# Connections.net
KiCad netlist of a schematic drawn in Altium Designer
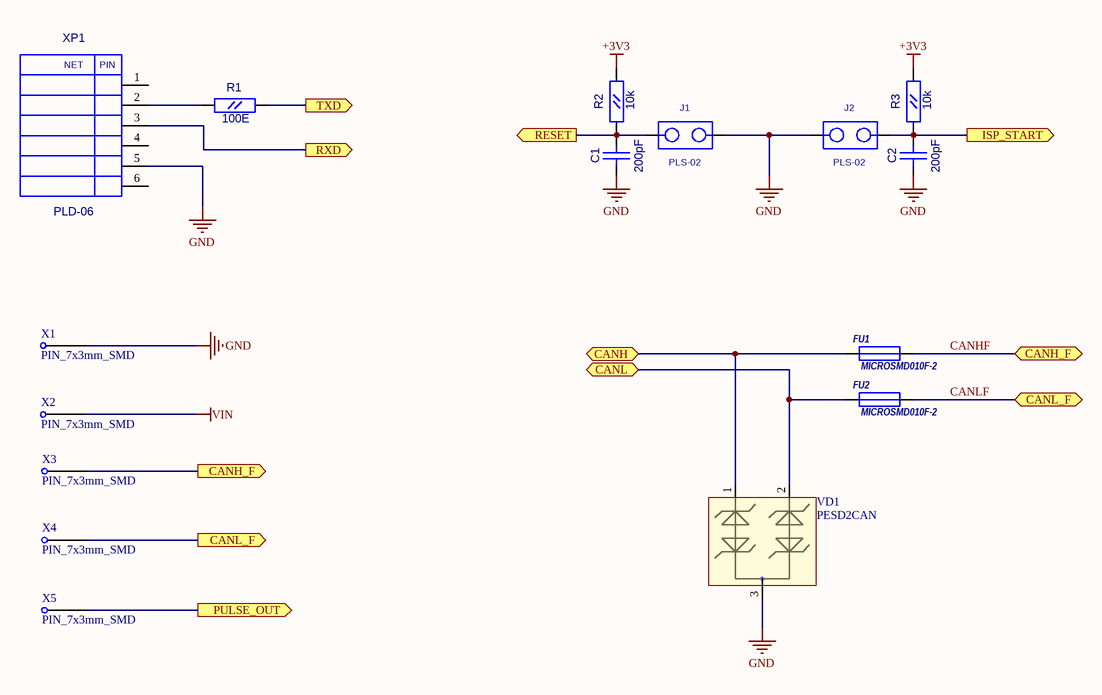
[diagram p0: Connections.SchDoc]

(export (version "E")
  (design (tool "Eeschema 10.0.6"))
  (components
    (comp (ref "C1")
      (value "200pF")
      (footprint "CC0603")
      (description "CC0603")
      (libsource (lib "gprs_modem_2") (part "CC0603"))
    )
    (comp (ref "C2")
      (value "200pF")
      (footprint "CC0603")
      (description "CC0603")
      (libsource (lib "gprs_modem_2") (part "CC0603"))
    )
    (comp (ref "FU1")
      (value "MICROSMD010F-2")
      (footprint "RC1210")
      (description "MICROSMD")
      (libsource (lib "gprs_modem_2") (part "MICROSMD"))
    )
    (comp (ref "FU2")
      (value "MICROSMD010F-2")
      (footprint "RC1210")
      (description "MICROSMD")
      (libsource (lib "gprs_modem_2") (part "MICROSMD"))
    )
    (comp (ref "J1") (value "PLS-02") (footprint "PLS-02") (libsource (lib "gprs_modem_2") (part "PLS-02")))
    (comp (ref "J2") (value "PLS-02") (footprint "PLS-02") (libsource (lib "gprs_modem_2") (part "PLS-02")))
    (comp (ref "R1")
      (value "100E")
      (footprint "RC0603")
      (description "RC0603")
      (libsource (lib "gprs_modem_2") (part "RC0603"))
    )
    (comp (ref "R2")
      (value "10k")
      (footprint "RC0603")
      (description "RC0603")
      (libsource (lib "gprs_modem_2") (part "RC0603"))
    )
    (comp (ref "R3")
      (value "10k")
      (footprint "RC0603")
      (description "RC0603")
      (libsource (lib "gprs_modem_2") (part "RC0603"))
    )
    (comp (ref "VD1")
      (value "PESD2CAN")
      (footprint "SOT-23(123)")
      (description "TVS for CAN")
      (libsource (lib "gprs_modem_2") (part "PESD2CAN"))
    )
    (comp (ref "X1")
      (value "PIN_7x3mm_SMD")
      (footprint "PIN_7x3mm_SMD")
      (libsource (lib "gprs_modem_2") (part "PIN_7x3mm_SMD"))
    )
    (comp (ref "X2")
      (value "PIN_7x3mm_SMD")
      (footprint "PIN_7x3mm_SMD")
      (libsource (lib "gprs_modem_2") (part "PIN_7x3mm_SMD"))
    )
    (comp (ref "X3")
      (value "PIN_7x3mm_SMD")
      (footprint "PIN_7x3mm_SMD")
      (libsource (lib "gprs_modem_2") (part "PIN_7x3mm_SMD"))
    )
    (comp (ref "X4")
      (value "PIN_7x3mm_SMD")
      (footprint "PIN_7x3mm_SMD")
      (libsource (lib "gprs_modem_2") (part "PIN_7x3mm_SMD"))
    )
    (comp (ref "X5")
      (value "PIN_7x3mm_SMD")
      (footprint "PIN_7x3mm_SMD")
      (libsource (lib "gprs_modem_2") (part "PIN_7x3mm_SMD"))
    )
    (comp (ref "XP1")
      (value "PLD-06")
      (footprint "PIN6")
      (description "PLD06")
      (libsource (lib "gprs_modem_2") (part "PLD-06"))
    )
  )
  (nets
    (net (code "1") (name "+3V3") (class "Default")
      (node (ref "R2") (pin "2") (pinfunction "B_2") (pintype "passive"))
      (node (ref "R3") (pin "2") (pinfunction "B_2") (pintype "passive"))
    )
    (net (code "2") (name "/CANH") (class "Default")
      (node (ref "FU1") (pin "1") (pintype "passive"))
      (node (ref "VD1") (pin "1") (pinfunction "1_1") (pintype "passive"))
    )
    (net (code "3") (name "/CANHF") (class "Default")
      (node (ref "FU1") (pin "2") (pintype "passive"))
      (node (ref "X3") (pin "1") (pinfunction "1_1") (pintype "passive"))
    )
    (net (code "4") (name "/CANL") (class "Default")
      (node (ref "FU2") (pin "1") (pintype "passive"))
      (node (ref "VD1") (pin "2") (pinfunction "2_2") (pintype "passive"))
    )
    (net (code "5") (name "/CANLF") (class "Default")
      (node (ref "FU2") (pin "2") (pintype "passive"))
      (node (ref "X4") (pin "1") (pinfunction "1_1") (pintype "passive"))
    )
    (net (code "6") (name "/ISP_START") (class "Default")
      (node (ref "C2") (pin "2") (pinfunction "B_2") (pintype "passive"))
      (node (ref "J2") (pin "2") (pintype "passive"))
      (node (ref "R3") (pin "1") (pinfunction "A_1") (pintype "passive"))
    )
    (net (code "7") (name "/PULSE_OUT") (class "Default")
      (node (ref "X5") (pin "1") (pinfunction "1_1") (pintype "passive"))
    )
    (net (code "8") (name "/RESET") (class "Default")
      (node (ref "C1") (pin "2") (pinfunction "B_2") (pintype "passive"))
      (node (ref "J1") (pin "1") (pintype "passive"))
      (node (ref "R2") (pin "1") (pinfunction "A_1") (pintype "passive"))
    )
    (net (code "9") (name "/RXD") (class "Default")
      (node (ref "XP1") (pin "3") (pinfunction "3_3") (pintype "passive"))
    )
    (net (code "10") (name "/TXD") (class "Default")
      (node (ref "R1") (pin "2") (pinfunction "B_2") (pintype "passive"))
    )
    (net (code "11") (name "GND") (class "Default")
      (node (ref "C1") (pin "1") (pinfunction "A_1") (pintype "passive"))
      (node (ref "C2") (pin "1") (pinfunction "A_1") (pintype "passive"))
      (node (ref "J1") (pin "2") (pintype "passive"))
      (node (ref "J2") (pin "1") (pintype "passive"))
      (node (ref "VD1") (pin "3") (pinfunction "3_3") (pintype "passive"))
      (node (ref "X1") (pin "1") (pinfunction "1_1") (pintype "passive"))
      (node (ref "XP1") (pin "5") (pinfunction "5_5") (pintype "passive"))
    )
    (net (code "12") (name "Net-(R1-A)") (class "Default")
      (node (ref "R1") (pin "1") (pinfunction "A_1") (pintype "passive"))
      (node (ref "XP1") (pin "2") (pinfunction "2_2") (pintype "passive"))
    )
    (net (code "13") (name "VIN") (class "Default")
      (node (ref "X2") (pin "1") (pinfunction "1_1") (pintype "passive"))
    )
    (net (code "14") (name "unconnected-(XP1-Pad1)") (class "Default")
      (node (ref "XP1") (pin "1") (pinfunction "1_1") (pintype "passive"))
    )
    (net (code "15") (name "unconnected-(XP1-Pad4)") (class "Default")
      (node (ref "XP1") (pin "4") (pinfunction "4_4") (pintype "passive"))
    )
    (net (code "16") (name "unconnected-(XP1-Pad6)") (class "Default")
      (node (ref "XP1") (pin "6") (pinfunction "6_6") (pintype "passive"))
    )
  )
)
